# LionIRVT-PMP15043-2.net
KiCad netlist of a schematic drawn in Altium Designer
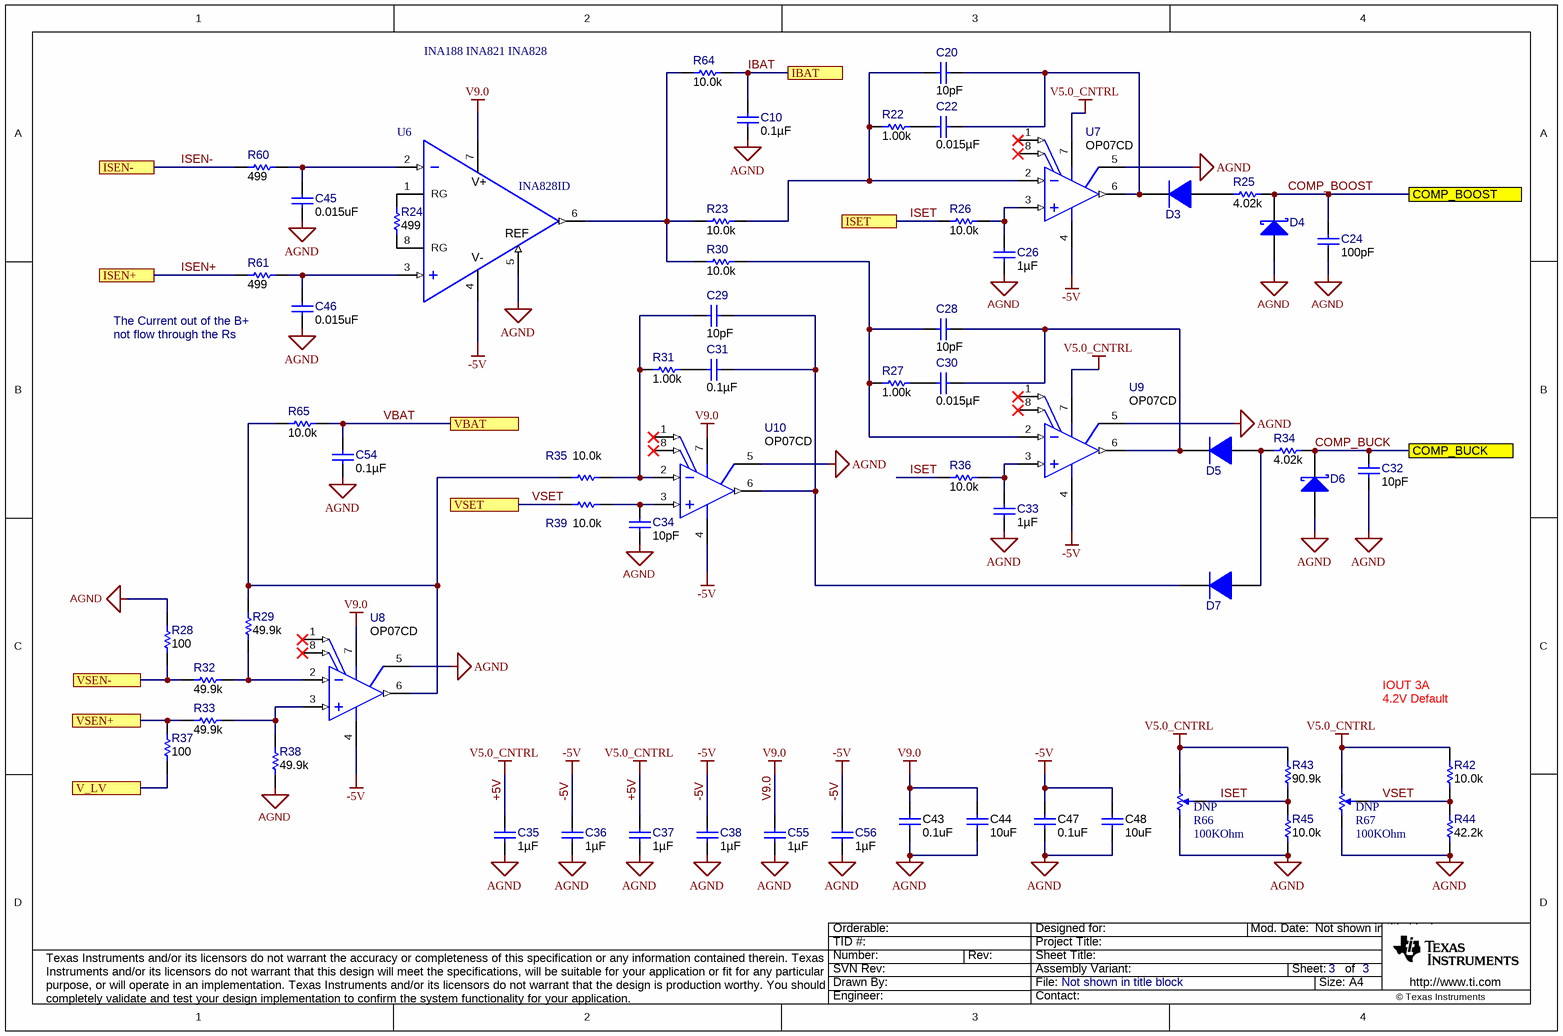
[diagram p0: LionIRVT-PMP15043-2.SchDoc]

(export (version "E")
  (design (tool "Eeschema 10.0.6"))
  (components
    (comp (ref "C10")
      (value "GRM155R61C104KA88D")
      (footprint "0402")
      (description "CAP, CERM, 0.1 µF, 16 V, +/- 10%, X5R, 0402")
      (fields
        (field (name "VALUEDISPLAYED") "0.1µF")
        (field (name "MANUFACTURER") "MuRata")
        (field (name "PUBLISHER") "Texas Instruments")
      )
      (libsource (lib "Capacitor_Ceramic") (part "GRM155R61C104KA88D"))
    )
    (comp (ref "C20")
      (value "GRM1555C1H100JA01D")
      (footprint "0402")
      (description "CAP, CERM, 10 pF, 50 V,+/- 5%, C0G/NP0, 0402")
      (fields
        (field (name "VALUEDISPLAYED") "10pF")
        (field (name "MANUFACTURER") "MuRata")
        (field (name "PUBLISHER") "Texas Instruments")
      )
      (libsource (lib "Capacitor_Ceramic") (part "GRM1555C1H100JA01D"))
    )
    (comp (ref "C22")
      (value "GRM155R71C153JA01D")
      (footprint "0402")
      (description "CAP, CERM, 0.015 µF, 16 V,+/- 5%, X7R, 0402")
      (fields
        (field (name "VALUEDISPLAYED") "0.015µF")
        (field (name "MANUFACTURER") "MuRata")
        (field (name "PUBLISHER") "Texas Instruments")
      )
      (libsource (lib "Capacitor_Ceramic") (part "GRM155R71C153JA01D"))
    )
    (comp (ref "C24")
      (value "GRM1555C1H101JA01D")
      (footprint "0402")
      (description "CAP, CERM, 100 pF, 50 V,+/- 5%, C0G/NP0, 0402")
      (fields
        (field (name "VALUEDISPLAYED") "100pF")
        (field (name "MANUFACTURER") "MuRata")
        (field (name "PUBLISHER") "Texas Instruments")
      )
      (libsource (lib "Capacitor_Ceramic") (part "GRM1555C1H101JA01D"))
    )
    (comp (ref "C26")
      (value "GRM155R70J105KA12D")
      (footprint "0402")
      (description "CAP, CERM, 1 µF, 6.3 V,+/- 10%, X7R, 0402")
      (fields
        (field (name "VALUEDISPLAYED") "1µF")
        (field (name "MANUFACTURER") "MuRata")
        (field (name "PUBLISHER") "Texas Instruments")
      )
      (libsource (lib "Capacitor_Ceramic") (part "GRM155R70J105KA12D"))
    )
    (comp (ref "C28")
      (value "GRM1555C1H100JA01D")
      (footprint "0402")
      (description "CAP, CERM, 10 pF, 50 V,+/- 5%, C0G/NP0, 0402")
      (fields
        (field (name "VALUEDISPLAYED") "10pF")
        (field (name "MANUFACTURER") "MuRata")
        (field (name "PUBLISHER") "Texas Instruments")
      )
      (libsource (lib "Capacitor_Ceramic") (part "GRM1555C1H100JA01D"))
    )
    (comp (ref "C29")
      (value "GRM1555C1H100JA01D")
      (footprint "0402")
      (description "CAP, CERM, 10 pF, 50 V,+/- 5%, C0G/NP0, 0402")
      (fields
        (field (name "VALUEDISPLAYED") "10pF")
        (field (name "MANUFACTURER") "MuRata")
        (field (name "PUBLISHER") "Texas Instruments")
      )
      (libsource (lib "Capacitor_Ceramic") (part "GRM1555C1H100JA01D"))
    )
    (comp (ref "C30")
      (value "GRM155R71C153JA01D")
      (footprint "0402")
      (description "CAP, CERM, 0.015 µF, 16 V,+/- 5%, X7R, 0402")
      (fields
        (field (name "VALUEDISPLAYED") "0.015µF")
        (field (name "MANUFACTURER") "MuRata")
        (field (name "PUBLISHER") "Texas Instruments")
      )
      (libsource (lib "Capacitor_Ceramic") (part "GRM155R71C153JA01D"))
    )
    (comp (ref "C31")
      (value "GRM155R61C104KA88D")
      (footprint "0402")
      (description "CAP, CERM, 0.1 µF, 16 V, +/- 10%, X5R, 0402")
      (fields
        (field (name "VALUEDISPLAYED") "0.1µF")
        (field (name "MANUFACTURER") "MuRata")
        (field (name "PUBLISHER") "Texas Instruments")
      )
      (libsource (lib "Capacitor_Ceramic") (part "GRM155R61C104KA88D"))
    )
    (comp (ref "C32")
      (value "GRM1555C1H100JA01D")
      (footprint "0402")
      (description "CAP, CERM, 10 pF, 50 V,+/- 5%, C0G/NP0, 0402")
      (fields
        (field (name "VALUEDISPLAYED") "10pF")
        (field (name "MANUFACTURER") "MuRata")
        (field (name "PUBLISHER") "Texas Instruments")
      )
      (libsource (lib "Capacitor_Ceramic") (part "GRM1555C1H100JA01D"))
    )
    (comp (ref "C33")
      (value "GRM155R70J105KA12D")
      (footprint "0402")
      (description "CAP, CERM, 1 µF, 6.3 V,+/- 10%, X7R, 0402")
      (fields
        (field (name "VALUEDISPLAYED") "1µF")
        (field (name "MANUFACTURER") "MuRata")
        (field (name "PUBLISHER") "Texas Instruments")
      )
      (libsource (lib "Capacitor_Ceramic") (part "GRM155R70J105KA12D"))
    )
    (comp (ref "C34")
      (value "GRM1555C1H100JA01D")
      (footprint "0402")
      (description "CAP, CERM, 10 pF, 50 V,+/- 5%, C0G/NP0, 0402")
      (fields
        (field (name "VALUEDISPLAYED") "10pF")
        (field (name "MANUFACTURER") "MuRata")
        (field (name "PUBLISHER") "Texas Instruments")
      )
      (libsource (lib "Capacitor_Ceramic") (part "GRM1555C1H100JA01D"))
    )
    (comp (ref "C35")
      (value "GRM155R61A105KE15D")
      (footprint "0402")
      (description "CAP, CERM, 1 µF, 10 V,+/- 10%, X5R, 0402")
      (fields
        (field (name "VALUEDISPLAYED") "1µF")
        (field (name "MANUFACTURER") "MuRata")
        (field (name "PUBLISHER") "Texas Instruments")
      )
      (libsource (lib "Capacitor_Ceramic") (part "GRM155R61A105KE15D"))
    )
    (comp (ref "C36")
      (value "GRM155R61A105KE15D")
      (footprint "0402")
      (description "CAP, CERM, 1 µF, 10 V,+/- 10%, X5R, 0402")
      (fields
        (field (name "VALUEDISPLAYED") "1µF")
        (field (name "MANUFACTURER") "MuRata")
        (field (name "PUBLISHER") "Texas Instruments")
      )
      (libsource (lib "Capacitor_Ceramic") (part "GRM155R61A105KE15D"))
    )
    (comp (ref "C37")
      (value "GRM155R61A105KE15D")
      (footprint "0402")
      (description "CAP, CERM, 1 µF, 10 V,+/- 10%, X5R, 0402")
      (fields
        (field (name "VALUEDISPLAYED") "1µF")
        (field (name "MANUFACTURER") "MuRata")
        (field (name "PUBLISHER") "Texas Instruments")
      )
      (libsource (lib "Capacitor_Ceramic") (part "GRM155R61A105KE15D"))
    )
    (comp (ref "C38")
      (value "GRM155R61A105KE15D")
      (footprint "0402")
      (description "CAP, CERM, 1 µF, 10 V,+/- 10%, X5R, 0402")
      (fields
        (field (name "VALUEDISPLAYED") "1µF")
        (field (name "MANUFACTURER") "MuRata")
        (field (name "PUBLISHER") "Texas Instruments")
      )
      (libsource (lib "Capacitor_Ceramic") (part "GRM155R61A105KE15D"))
    )
    (comp (ref "C43")
      (value "Capacitor")
      (footprint "0603")
      (description "CAP, CERM, 0.1 uF, 25 V, +/- 5%, X7R, 0603")
      (fields
        (field (name "PARTNUMBER") "06033C104JAT2A")
        (field (name "VALUEDISPLAYED") "0.1uF")
        (field (name "MANUFACTURER") "AVX")
        (field (name "PUBLISHER") "Texas Instruments")
      )
      (libsource (lib "Altium Vault - TI") (part "CMP-0006752-5"))
    )
    (comp (ref "C44")
      (value "Capacitor")
      (footprint "0805_HV")
      (description "CAP, CERM, 10 uF, 10 V, +/- 10%, X7R, 0805")
      (fields
        (field (name "PARTNUMBER") "GRM21BR71A106KE51L")
        (field (name "VALUEDISPLAYED") "10uF")
        (field (name "MANUFACTURER") "MuRata")
        (field (name "PUBLISHER") "Texas Instruments")
      )
      (libsource (lib "Altium Vault - TI") (part "CMP-0008315-2"))
    )
    (comp (ref "C45")
      (value "Capacitor")
      (footprint "0603")
      (description "CAP, CERM, 0.015 uF, 16 V, +/- 10%, X7R, 0603")
      (fields
        (field (name "PARTNUMBER") "GRM188R71C153KA01D")
        (field (name "VALUEDISPLAYED") "0.015uF")
        (field (name "MANUFACTURER") "MuRata")
        (field (name "PUBLISHER") "Texas Instruments")
      )
      (libsource (lib "Altium Vault - TI") (part "CMP-0007383-5"))
    )
    (comp (ref "C46")
      (value "Capacitor")
      (footprint "0603")
      (description "CAP, CERM, 0.015 uF, 16 V, +/- 10%, X7R, 0603")
      (fields
        (field (name "PARTNUMBER") "GRM188R71C153KA01D")
        (field (name "VALUEDISPLAYED") "0.015uF")
        (field (name "MANUFACTURER") "MuRata")
        (field (name "PUBLISHER") "Texas Instruments")
      )
      (libsource (lib "Altium Vault - TI") (part "CMP-0007383-5"))
    )
    (comp (ref "C47")
      (value "Capacitor")
      (footprint "0603")
      (description "CAP, CERM, 0.1 uF, 25 V, +/- 5%, X7R, 0603")
      (fields
        (field (name "PARTNUMBER") "06033C104JAT2A")
        (field (name "VALUEDISPLAYED") "0.1uF")
        (field (name "MANUFACTURER") "AVX")
        (field (name "PUBLISHER") "Texas Instruments")
      )
      (libsource (lib "Altium Vault - TI") (part "CMP-0006752-5"))
    )
    (comp (ref "C48")
      (value "Capacitor")
      (footprint "0805_HV")
      (description "CAP, CERM, 10 uF, 10 V, +/- 10%, X7R, 0805")
      (fields
        (field (name "PARTNUMBER") "GRM21BR71A106KE51L")
        (field (name "VALUEDISPLAYED") "10uF")
        (field (name "MANUFACTURER") "MuRata")
        (field (name "PUBLISHER") "Texas Instruments")
      )
      (libsource (lib "Altium Vault - TI") (part "CMP-0008315-2"))
    )
    (comp (ref "C54")
      (value "GRM155R61C104KA88D")
      (footprint "0402")
      (description "CAP, CERM, 0.1 µF, 16 V, +/- 10%, X5R, 0402")
      (fields
        (field (name "VALUEDISPLAYED") "0.1µF")
        (field (name "MANUFACTURER") "MuRata")
        (field (name "PUBLISHER") "Texas Instruments")
      )
      (libsource (lib "Capacitor_Ceramic") (part "GRM155R61C104KA88D"))
    )
    (comp (ref "C55")
      (value "GRM155R61A105KE15D")
      (footprint "0402")
      (description "CAP, CERM, 1 µF, 10 V,+/- 10%, X5R, 0402")
      (fields
        (field (name "VALUEDISPLAYED") "1µF")
        (field (name "MANUFACTURER") "MuRata")
        (field (name "PUBLISHER") "Texas Instruments")
      )
      (libsource (lib "Capacitor_Ceramic") (part "GRM155R61A105KE15D"))
    )
    (comp (ref "C56")
      (value "GRM155R61A105KE15D")
      (footprint "0402")
      (description "CAP, CERM, 1 µF, 10 V,+/- 10%, X5R, 0402")
      (fields
        (field (name "VALUEDISPLAYED") "1µF")
        (field (name "MANUFACTURER") "MuRata")
        (field (name "PUBLISHER") "Texas Instruments")
      )
      (libsource (lib "Capacitor_Ceramic") (part "GRM155R61A105KE15D"))
    )
    (comp (ref "D3")
      (value "1N4148X-TP")
      (footprint "SOD-523")
      (description "Diode, Switching, 75 V, 0.3 A, SOD-523")
      (fields
        (field (name "MANUFACTURER") "Micro Commercial Components")
        (field (name "PUBLISHER") "Texas Instruments")
      )
      (libsource (lib "Diode") (part "1N4148X-TP"))
    )
    (comp (ref "D4")
      (value "BAT54WS-7-F")
      (footprint "SOD-323")
      (description "Diode, Schottky, 30 V, 0.2 A, SOD-323")
      (fields (field (name "MANUFACTURER") "Diodes Inc.") (field (name "PUBLISHER") "Texas Instruments"))
      (libsource (lib "Diode") (part "BAT54WS-7-F"))
    )
    (comp (ref "D5")
      (value "1N4148X-TP")
      (footprint "SOD-523")
      (description "Diode, Switching, 75 V, 0.3 A, SOD-523")
      (fields
        (field (name "MANUFACTURER") "Micro Commercial Components")
        (field (name "PUBLISHER") "Texas Instruments")
      )
      (libsource (lib "Diode") (part "1N4148X-TP"))
    )
    (comp (ref "D6")
      (value "BAT54WS-7-F")
      (footprint "SOD-323")
      (description "Diode, Schottky, 30 V, 0.2 A, SOD-323")
      (fields (field (name "MANUFACTURER") "Diodes Inc.") (field (name "PUBLISHER") "Texas Instruments"))
      (libsource (lib "Diode") (part "BAT54WS-7-F"))
    )
    (comp (ref "D7")
      (value "1N4148X-TP")
      (footprint "SOD-523")
      (description "Diode, Switching, 75 V, 0.3 A, SOD-523")
      (fields
        (field (name "MANUFACTURER") "Micro Commercial Components")
        (field (name "PUBLISHER") "Texas Instruments")
      )
      (libsource (lib "Diode") (part "1N4148X-TP"))
    )
    (comp (ref "R22")
      (value "CRCW04021K00FKED")
      (footprint "0402")
      (description "RES, 1.00 k, 1%, 0.063 W, 0402")
      (fields
        (field (name "VALUEDISPLAYED") "1.00k")
        (field (name "MANUFACTURER") "Vishay-Dale")
        (field (name "PUBLISHER") "Texas Instruments")
      )
      (libsource (lib "Resistor_0402") (part "CRCW04021K00FKED"))
    )
    (comp (ref "R23")
      (value "CRCW040210K0FKED")
      (footprint "0402")
      (description "RES, 10.0 k, 1%, 0.063 W, 0402")
      (fields
        (field (name "VALUEDISPLAYED") "10.0k")
        (field (name "MANUFACTURER") "Vishay-Dale")
        (field (name "PUBLISHER") "Texas Instruments")
      )
      (libsource (lib "Resistor_0402") (part "CRCW040210K0FKED"))
    )
    (comp (ref "R24")
      (value "RC0603FR-07499RL")
      (footprint "0603")
      (description "RES, 499, 1%, 0.1 W, 0603")
      (fields
        (field (name "VALUEDISPLAYED") "499")
        (field (name "MANUFACTURER") "Yageo America")
        (field (name "PUBLISHER") "Texas Instruments")
      )
      (libsource (lib "Resistor_0603") (part "RC0603FR-07499RL"))
    )
    (comp (ref "R25")
      (value "CRCW04024K02FKED")
      (footprint "0402")
      (description "RES, 4.02 k, 1%, 0.063 W, 0402")
      (fields
        (field (name "VALUEDISPLAYED") "4.02k")
        (field (name "MANUFACTURER") "Vishay-Dale")
        (field (name "PUBLISHER") "Texas Instruments")
      )
      (libsource (lib "Resistor_0402") (part "CRCW04024K02FKED"))
    )
    (comp (ref "R26")
      (value "CRCW040210K0FKED")
      (footprint "0402")
      (description "RES, 10.0 k, 1%, 0.063 W, 0402")
      (fields
        (field (name "VALUEDISPLAYED") "10.0k")
        (field (name "MANUFACTURER") "Vishay-Dale")
        (field (name "PUBLISHER") "Texas Instruments")
      )
      (libsource (lib "Resistor_0402") (part "CRCW040210K0FKED"))
    )
    (comp (ref "R27")
      (value "CRCW04021K00FKED")
      (footprint "0402")
      (description "RES, 1.00 k, 1%, 0.063 W, 0402")
      (fields
        (field (name "VALUEDISPLAYED") "1.00k")
        (field (name "MANUFACTURER") "Vishay-Dale")
        (field (name "PUBLISHER") "Texas Instruments")
      )
      (libsource (lib "Resistor_0402") (part "CRCW04021K00FKED"))
    )
    (comp (ref "R28")
      (value "CRCW0402100RFKED")
      (footprint "0402")
      (description "RES, 100, 1%, 0.063 W, 0402")
      (fields
        (field (name "VALUEDISPLAYED") "100")
        (field (name "MANUFACTURER") "Vishay-Dale")
        (field (name "PUBLISHER") "Texas Instruments")
      )
      (libsource (lib "Resistor_0402") (part "CRCW0402100RFKED"))
    )
    (comp (ref "R29")
      (value "CRCW040251K1FKED")
      (footprint "0402")
      (description "RES, 51.1 k, 1%, 0.063 W, 0402")
      (fields
        (field (name "VALUEDISPLAYED") "49.9k")
        (field (name "MANUFACTURER") "Vishay-Dale")
        (field (name "PUBLISHER") "Texas Instruments")
      )
      (libsource (lib "Resistor_0402") (part "CRCW040251K1FKED"))
    )
    (comp (ref "R30")
      (value "CRCW040210K0FKED")
      (footprint "0402")
      (description "RES, 10.0 k, 1%, 0.063 W, 0402")
      (fields
        (field (name "VALUEDISPLAYED") "10.0k")
        (field (name "MANUFACTURER") "Vishay-Dale")
        (field (name "PUBLISHER") "Texas Instruments")
      )
      (libsource (lib "Resistor_0402") (part "CRCW040210K0FKED"))
    )
    (comp (ref "R31")
      (value "CRCW04021K00FKED")
      (footprint "0402")
      (description "RES, 1.00 k, 1%, 0.063 W, 0402")
      (fields
        (field (name "VALUEDISPLAYED") "1.00k")
        (field (name "MANUFACTURER") "Vishay-Dale")
        (field (name "PUBLISHER") "Texas Instruments")
      )
      (libsource (lib "Resistor_0402") (part "CRCW04021K00FKED"))
    )
    (comp (ref "R32")
      (value "CRCW040251K1FKED")
      (footprint "0402")
      (description "RES, 51.1 k, 1%, 0.063 W, 0402")
      (fields
        (field (name "VALUEDISPLAYED") "49.9k")
        (field (name "MANUFACTURER") "Vishay-Dale")
        (field (name "PUBLISHER") "Texas Instruments")
      )
      (libsource (lib "Resistor_0402") (part "CRCW040251K1FKED"))
    )
    (comp (ref "R33")
      (value "CRCW040251K1FKED")
      (footprint "0402")
      (description "RES, 51.1 k, 1%, 0.063 W, 0402")
      (fields
        (field (name "VALUEDISPLAYED") "49.9k")
        (field (name "MANUFACTURER") "Vishay-Dale")
        (field (name "PUBLISHER") "Texas Instruments")
      )
      (libsource (lib "Resistor_0402") (part "CRCW040251K1FKED"))
    )
    (comp (ref "R34")
      (value "CRCW04024K02FKED")
      (footprint "0402")
      (description "RES, 4.02 k, 1%, 0.063 W, 0402")
      (fields
        (field (name "VALUEDISPLAYED") "4.02k")
        (field (name "MANUFACTURER") "Vishay-Dale")
        (field (name "PUBLISHER") "Texas Instruments")
      )
      (libsource (lib "Resistor_0402") (part "CRCW04024K02FKED"))
    )
    (comp (ref "R35")
      (value "CRCW040210K0FKED")
      (footprint "0402")
      (description "RES, 10.0 k, 1%, 0.063 W, 0402")
      (fields
        (field (name "VALUEDISPLAYED") "10.0k")
        (field (name "MANUFACTURER") "Vishay-Dale")
        (field (name "PUBLISHER") "Texas Instruments")
      )
      (libsource (lib "Resistor_0402") (part "CRCW040210K0FKED"))
    )
    (comp (ref "R36")
      (value "CRCW040210K0FKED")
      (footprint "0402")
      (description "RES, 10.0 k, 1%, 0.063 W, 0402")
      (fields
        (field (name "VALUEDISPLAYED") "10.0k")
        (field (name "MANUFACTURER") "Vishay-Dale")
        (field (name "PUBLISHER") "Texas Instruments")
      )
      (libsource (lib "Resistor_0402") (part "CRCW040210K0FKED"))
    )
    (comp (ref "R37")
      (value "CRCW0402100RFKED")
      (footprint "0402")
      (description "RES, 100, 1%, 0.063 W, 0402")
      (fields
        (field (name "VALUEDISPLAYED") "100")
        (field (name "MANUFACTURER") "Vishay-Dale")
        (field (name "PUBLISHER") "Texas Instruments")
      )
      (libsource (lib "Resistor_0402") (part "CRCW0402100RFKED"))
    )
    (comp (ref "R38")
      (value "CRCW040251K1FKED")
      (footprint "0402")
      (description "RES, 51.1 k, 1%, 0.063 W, 0402")
      (fields
        (field (name "VALUEDISPLAYED") "49.9k")
        (field (name "MANUFACTURER") "Vishay-Dale")
        (field (name "PUBLISHER") "Texas Instruments")
      )
      (libsource (lib "Resistor_0402") (part "CRCW040251K1FKED"))
    )
    (comp (ref "R39")
      (value "CRCW040210K0FKED")
      (footprint "0402")
      (description "RES, 10.0 k, 1%, 0.063 W, 0402")
      (fields
        (field (name "VALUEDISPLAYED") "10.0k")
        (field (name "MANUFACTURER") "Vishay-Dale")
        (field (name "PUBLISHER") "Texas Instruments")
      )
      (libsource (lib "Resistor_0402") (part "CRCW040210K0FKED"))
    )
    (comp (ref "R42")
      (value "CRCW040210K0FKED")
      (footprint "0402")
      (description "RES, 10.0 k, 1%, 0.063 W, 0402")
      (fields
        (field (name "VALUEDISPLAYED") "10.0k")
        (field (name "MANUFACTURER") "Vishay-Dale")
        (field (name "PUBLISHER") "Texas Instruments")
      )
      (libsource (lib "Resistor_0402") (part "CRCW040210K0FKED"))
    )
    (comp (ref "R43")
      (value "CRCW040290K9FKED")
      (footprint "0402")
      (description "RES, 90.9 k, 1%, 0.063 W, 0402")
      (fields
        (field (name "VALUEDISPLAYED") "90.9k")
        (field (name "MANUFACTURER") "Vishay-Dale")
        (field (name "PUBLISHER") "Texas Instruments")
      )
      (libsource (lib "Resistor_0402") (part "CRCW040290K9FKED"))
    )
    (comp (ref "R44")
      (value "CRCW040242K2FKED")
      (footprint "0402")
      (description "RES, 42.2 k, 1%, 0.063 W, 0402")
      (fields
        (field (name "VALUEDISPLAYED") "42.2k")
        (field (name "MANUFACTURER") "Vishay-Dale")
        (field (name "PUBLISHER") "Texas Instruments")
      )
      (libsource (lib "Resistor_0402") (part "CRCW040242K2FKED"))
    )
    (comp (ref "R45")
      (value "CRCW040210K0FKED")
      (footprint "0402")
      (description "RES, 10.0 k, 1%, 0.063 W, 0402")
      (fields
        (field (name "VALUEDISPLAYED") "10.0k")
        (field (name "MANUFACTURER") "Vishay-Dale")
        (field (name "PUBLISHER") "Texas Instruments")
      )
      (libsource (lib "Resistor_0402") (part "CRCW040210K0FKED"))
    )
    (comp (ref "R60")
      (value "Resistor")
      (footprint "0603")
      (description "RES, 499, 1%, 0.1 W, AEC-Q200 Grade 0, 0603")
      (fields
        (field (name "PARTNUMBER") "CRCW0603499RFKEA")
        (field (name "VALUEDISPLAYED") "499")
        (field (name "MANUFACTURER") "Vishay-Dale")
      )
      (libsource (lib "Altium Vault - TI") (part "CMP-0022446-5"))
    )
    (comp (ref "R61")
      (value "Resistor")
      (footprint "0603")
      (description "RES, 499, 1%, 0.1 W, AEC-Q200 Grade 0, 0603")
      (fields
        (field (name "PARTNUMBER") "CRCW0603499RFKEA")
        (field (name "VALUEDISPLAYED") "499")
        (field (name "MANUFACTURER") "Vishay-Dale")
      )
      (libsource (lib "Altium Vault - TI") (part "CMP-0022446-5"))
    )
    (comp (ref "R64")
      (value "CRCW040210K0FKED")
      (footprint "0402")
      (description "RES, 10.0 k, 1%, 0.063 W, 0402")
      (fields
        (field (name "VALUEDISPLAYED") "10.0k")
        (field (name "MANUFACTURER") "Vishay-Dale")
        (field (name "PUBLISHER") "Texas Instruments")
      )
      (libsource (lib "Resistor_0402") (part "CRCW040210K0FKED"))
    )
    (comp (ref "R65")
      (value "CRCW040210K0FKED")
      (footprint "0402")
      (description "RES, 10.0 k, 1%, 0.063 W, 0402")
      (fields
        (field (name "VALUEDISPLAYED") "10.0k")
        (field (name "MANUFACTURER") "Vishay-Dale")
        (field (name "PUBLISHER") "Texas Instruments")
      )
      (libsource (lib "Resistor_0402") (part "CRCW040210K0FKED"))
    )
    (comp (ref "R66")
      (value "TC33X-2-104E")
      (footprint "BOUR-TC33X-2_V")
      (description "Trimming Potentiometer, 100000 Ohm, -40 to 100 degC, 3-Pin SMD, RoHS, Tape and Reel")
      (fields
        (field (name "TOLERANCE") "25%")
        (field (name "RESISTANCE") "100KOhm")
        (field (name "MANUFACTURER") "Bourns")
      )
      (libsource (lib "Altium Content Vault") (part "RES-ADJ-3_A"))
    )
    (comp (ref "R67")
      (value "TC33X-2-104E")
      (footprint "BOUR-TC33X-2_V")
      (description "Trimming Potentiometer, 100k Ohm, -40 to 100 degC, 3-Pin SMD, RoHS, Tape and Reel")
      (fields
        (field (name "TOLERANCE") "25%")
        (field (name "RESISTANCE") "100KOhm")
        (field (name "MANUFACTURER") "Bourns")
      )
      (libsource (lib "Altium Content Vault") (part "RES-ADJ-3_A"))
    )
    (comp (ref "U6")
      (value "INA828ID")
      (footprint "D0008A_N")
      (description "50-uV Offset, 7-nV/√Hz Noise, Low-Power, Precision Instrumentation Amplifier, D0008A (SOIC-8)")
      (fields
        (field (name "ALTERNATE PARTNUMBER") "INA828IDR")
        (field (name "MANUFACTURER") "Texas Instruments")
        (field (name "PARTNUMBER") "INA828ID")
      )
      (libsource (lib "Altium Vault - TI") (part "CMP-0079943-1"))
    )
    (comp (ref "U7")
      (value "OP07CD")
      (footprint "D0008A_N")
      (fields
        (field (name "ALTERNATE PARTNUMBER") "Equivalent")
        (field (name "MANUFACTURER") "Texas Instruments")
      )
      (libsource (lib "TI Amplifiers and Linear Operational Amplifier General Purpose") (part "OP07CD"))
    )
    (comp (ref "U8")
      (value "OP07CD")
      (footprint "D0008A_N")
      (fields
        (field (name "ALTERNATE PARTNUMBER") "Equivalent")
        (field (name "MANUFACTURER") "Texas Instruments")
      )
      (libsource (lib "TI Amplifiers and Linear Operational Amplifier General Purpose") (part "OP07CD"))
    )
    (comp (ref "U9")
      (value "OP07CD")
      (footprint "D0008A_N")
      (fields
        (field (name "ALTERNATE PARTNUMBER") "Equivalent")
        (field (name "MANUFACTURER") "Texas Instruments")
      )
      (libsource (lib "TI Amplifiers and Linear Operational Amplifier General Purpose") (part "OP07CD"))
    )
    (comp (ref "U10")
      (value "OP07CD")
      (footprint "D0008A_N")
      (fields
        (field (name "ALTERNATE PARTNUMBER") "Equivalent")
        (field (name "MANUFACTURER") "Texas Instruments")
      )
      (libsource (lib "TI Amplifiers and Linear Operational Amplifier General Purpose") (part "OP07CD"))
    )
  )
  (nets
    (net (code "1") (name "-5V") (class "Default")
      (node (ref "C36") (pin "1") (pinfunction "1_1") (pintype "passive"))
      (node (ref "C38") (pin "1") (pinfunction "1_1") (pintype "passive"))
      (node (ref "C47") (pin "1") (pinfunction "1_1") (pintype "passive"))
      (node (ref "C48") (pin "1") (pinfunction "1_1") (pintype "passive"))
      (node (ref "C56") (pin "1") (pinfunction "1_1") (pintype "passive"))
      (node (ref "U10") (pin "4") (pinfunction "VCC-_4") (pintype "power_in"))
      (node (ref "U6") (pin "4") (pinfunction "V-_4") (pintype "power_in"))
      (node (ref "U7") (pin "4") (pinfunction "VCC-_4") (pintype "power_in"))
      (node (ref "U8") (pin "4") (pinfunction "VCC-_4") (pintype "power_in"))
      (node (ref "U9") (pin "4") (pinfunction "VCC-_4") (pintype "power_in"))
    )
    (net (code "2") (name "/COMP_BOOST") (class "Default")
      (node (ref "C24") (pin "1") (pinfunction "1_1") (pintype "passive"))
      (node (ref "D4") (pin "1") (pinfunction "K_1") (pintype "passive"))
      (node (ref "R25") (pin "1") (pinfunction "1_1") (pintype "passive"))
    )
    (net (code "3") (name "/COMP_BUCK") (class "Default")
      (node (ref "C32") (pin "1") (pinfunction "1_1") (pintype "passive"))
      (node (ref "D6") (pin "1") (pinfunction "K_1") (pintype "passive"))
      (node (ref "R34") (pin "1") (pinfunction "1_1") (pintype "passive"))
    )
    (net (code "4") (name "/IBAT") (class "Default")
      (node (ref "C10") (pin "1") (pinfunction "1_1") (pintype "passive"))
      (node (ref "R64") (pin "2") (pinfunction "2_2") (pintype "passive"))
    )
    (net (code "5") (name "/ISEN+") (class "Default")
      (node (ref "R61") (pin "2") (pinfunction "2_2") (pintype "passive"))
    )
    (net (code "6") (name "/ISEN-") (class "Default")
      (node (ref "R60") (pin "2") (pinfunction "2_2") (pintype "passive"))
    )
    (net (code "7") (name "/ISET") (class "Default")
      (node (ref "R26") (pin "2") (pinfunction "2_2") (pintype "passive"))
      (node (ref "R36") (pin "2") (pinfunction "2_2") (pintype "passive"))
      (node (ref "R43") (pin "1") (pinfunction "1_1") (pintype "passive"))
      (node (ref "R45") (pin "2") (pinfunction "2_2") (pintype "passive"))
      (node (ref "R66") (pin "2") (pinfunction "2_2") (pintype "passive"))
    )
    (net (code "8") (name "/VBAT") (class "Default")
      (node (ref "C54") (pin "1") (pinfunction "1_1") (pintype "passive"))
      (node (ref "R65") (pin "2") (pinfunction "2_2") (pintype "passive"))
    )
    (net (code "9") (name "/VSEN+") (class "Default")
      (node (ref "R33") (pin "1") (pinfunction "1_1") (pintype "passive"))
      (node (ref "R37") (pin "2") (pinfunction "2_2") (pintype "passive"))
    )
    (net (code "10") (name "/VSEN-") (class "Default")
      (node (ref "R28") (pin "1") (pinfunction "1_1") (pintype "passive"))
      (node (ref "R32") (pin "1") (pinfunction "1_1") (pintype "passive"))
    )
    (net (code "11") (name "/VSET") (class "Default")
      (node (ref "R39") (pin "2") (pinfunction "2_2") (pintype "passive"))
      (node (ref "R42") (pin "1") (pinfunction "1_1") (pintype "passive"))
      (node (ref "R44") (pin "2") (pinfunction "2_2") (pintype "passive"))
      (node (ref "R67") (pin "2") (pinfunction "2_2") (pintype "passive"))
    )
    (net (code "12") (name "/V_LV") (class "Default")
      (node (ref "R37") (pin "1") (pinfunction "1_1") (pintype "passive"))
    )
    (net (code "13") (name "AGND") (class "Default")
      (node (ref "C10") (pin "2") (pinfunction "2_2") (pintype "passive"))
      (node (ref "C24") (pin "2") (pinfunction "2_2") (pintype "passive"))
      (node (ref "C26") (pin "2") (pinfunction "2_2") (pintype "passive"))
      (node (ref "C32") (pin "2") (pinfunction "2_2") (pintype "passive"))
      (node (ref "C33") (pin "2") (pinfunction "2_2") (pintype "passive"))
      (node (ref "C34") (pin "2") (pinfunction "2_2") (pintype "passive"))
      (node (ref "C35") (pin "2") (pinfunction "2_2") (pintype "passive"))
      (node (ref "C36") (pin "2") (pinfunction "2_2") (pintype "passive"))
      (node (ref "C37") (pin "2") (pinfunction "2_2") (pintype "passive"))
      (node (ref "C38") (pin "2") (pinfunction "2_2") (pintype "passive"))
      (node (ref "C43") (pin "2") (pinfunction "2_2") (pintype "passive"))
      (node (ref "C44") (pin "2") (pinfunction "2_2") (pintype "passive"))
      (node (ref "C45") (pin "2") (pinfunction "2_2") (pintype "passive"))
      (node (ref "C46") (pin "2") (pinfunction "2_2") (pintype "passive"))
      (node (ref "C47") (pin "2") (pinfunction "2_2") (pintype "passive"))
      (node (ref "C48") (pin "2") (pinfunction "2_2") (pintype "passive"))
      (node (ref "C54") (pin "2") (pinfunction "2_2") (pintype "passive"))
      (node (ref "C55") (pin "2") (pinfunction "2_2") (pintype "passive"))
      (node (ref "C56") (pin "2") (pinfunction "2_2") (pintype "passive"))
      (node (ref "D4") (pin "2") (pinfunction "A_2") (pintype "passive"))
      (node (ref "D6") (pin "2") (pinfunction "A_2") (pintype "passive"))
      (node (ref "R28") (pin "2") (pinfunction "2_2") (pintype "passive"))
      (node (ref "R38") (pin "1") (pinfunction "1_1") (pintype "passive"))
      (node (ref "R44") (pin "1") (pinfunction "1_1") (pintype "passive"))
      (node (ref "R45") (pin "1") (pinfunction "1_1") (pintype "passive"))
      (node (ref "R66") (pin "1") (pinfunction "1_1") (pintype "passive"))
      (node (ref "R67") (pin "1") (pinfunction "1_1") (pintype "passive"))
      (node (ref "U10") (pin "5") (pinfunction "NC_5") (pintype "passive"))
      (node (ref "U6") (pin "5") (pinfunction "REF_5") (pintype "input"))
      (node (ref "U7") (pin "5") (pinfunction "NC_5") (pintype "passive"))
      (node (ref "U8") (pin "5") (pinfunction "NC_5") (pintype "passive"))
      (node (ref "U9") (pin "5") (pinfunction "NC_5") (pintype "passive"))
    )
    (net (code "14") (name "Net-(C22-Pad2)") (class "Default")
      (node (ref "C22") (pin "2") (pinfunction "2_2") (pintype "passive"))
      (node (ref "R22") (pin "2") (pinfunction "2_2") (pintype "passive"))
    )
    (net (code "15") (name "Net-(C30-Pad2)") (class "Default")
      (node (ref "C30") (pin "2") (pinfunction "2_2") (pintype "passive"))
      (node (ref "R27") (pin "2") (pinfunction "2_2") (pintype "passive"))
    )
    (net (code "16") (name "Net-(C31-Pad2)") (class "Default")
      (node (ref "C31") (pin "2") (pinfunction "2_2") (pintype "passive"))
      (node (ref "R31") (pin "2") (pinfunction "2_2") (pintype "passive"))
    )
    (net (code "17") (name "Net-(D3-A)") (class "Default")
      (node (ref "D3") (pin "2") (pinfunction "A_2") (pintype "passive"))
      (node (ref "R25") (pin "2") (pinfunction "2_2") (pintype "passive"))
    )
    (net (code "18") (name "Net-(D3-K)") (class "Default")
      (node (ref "C20") (pin "1") (pinfunction "1_1") (pintype "passive"))
      (node (ref "C22") (pin "1") (pinfunction "1_1") (pintype "passive"))
      (node (ref "D3") (pin "1") (pinfunction "K_1") (pintype "passive"))
      (node (ref "U7") (pin "6") (pinfunction "OUT_6") (pintype "output"))
    )
    (net (code "19") (name "Net-(D5-A)") (class "Default")
      (node (ref "D5") (pin "2") (pinfunction "A_2") (pintype "passive"))
      (node (ref "D7") (pin "2") (pinfunction "A_2") (pintype "passive"))
      (node (ref "R34") (pin "2") (pinfunction "2_2") (pintype "passive"))
    )
    (net (code "20") (name "Net-(D5-K)") (class "Default")
      (node (ref "C28") (pin "1") (pinfunction "1_1") (pintype "passive"))
      (node (ref "C30") (pin "1") (pinfunction "1_1") (pintype "passive"))
      (node (ref "D5") (pin "1") (pinfunction "K_1") (pintype "passive"))
      (node (ref "U9") (pin "6") (pinfunction "OUT_6") (pintype "output"))
    )
    (net (code "21") (name "Net-(D7-K)") (class "Default")
      (node (ref "C29") (pin "1") (pinfunction "1_1") (pintype "passive"))
      (node (ref "C31") (pin "1") (pinfunction "1_1") (pintype "passive"))
      (node (ref "D7") (pin "1") (pinfunction "K_1") (pintype "passive"))
      (node (ref "U10") (pin "6") (pinfunction "OUT_6") (pintype "output"))
    )
    (net (code "22") (name "Net-(R24-Pad1)") (class "Default")
      (node (ref "R24") (pin "1") (pinfunction "1_1") (pintype "passive"))
      (node (ref "U6") (pin "8") (pinfunction "RG_8") (pintype "passive"))
    )
    (net (code "23") (name "Net-(R24-Pad2)") (class "Default")
      (node (ref "R24") (pin "2") (pinfunction "2_2") (pintype "passive"))
      (node (ref "U6") (pin "1") (pinfunction "RG_1") (pintype "passive"))
    )
    (net (code "24") (name "Net-(U6-IN+)") (class "Default")
      (node (ref "C46") (pin "1") (pinfunction "1_1") (pintype "passive"))
      (node (ref "R61") (pin "1") (pinfunction "1_1") (pintype "passive"))
      (node (ref "U6") (pin "3") (pinfunction "IN+_3") (pintype "input"))
    )
    (net (code "25") (name "Net-(U6-IN-)") (class "Default")
      (node (ref "C45") (pin "1") (pinfunction "1_1") (pintype "passive"))
      (node (ref "R60") (pin "1") (pinfunction "1_1") (pintype "passive"))
      (node (ref "U6") (pin "2") (pinfunction "IN-_2") (pintype "input"))
    )
    (net (code "26") (name "Net-(U6-OUT)") (class "Default")
      (node (ref "R23") (pin "2") (pinfunction "2_2") (pintype "passive"))
      (node (ref "R30") (pin "1") (pinfunction "1_1") (pintype "passive"))
      (node (ref "R64") (pin "1") (pinfunction "1_1") (pintype "passive"))
      (node (ref "U6") (pin "6") (pinfunction "OUT_6") (pintype "output"))
    )
    (net (code "27") (name "Net-(U7-IN+)") (class "Default")
      (node (ref "C26") (pin "1") (pinfunction "1_1") (pintype "passive"))
      (node (ref "R26") (pin "1") (pinfunction "1_1") (pintype "passive"))
      (node (ref "U7") (pin "3") (pinfunction "IN+_3") (pintype "input"))
    )
    (net (code "28") (name "Net-(U7-IN-)") (class "Default")
      (node (ref "C20") (pin "2") (pinfunction "2_2") (pintype "passive"))
      (node (ref "R22") (pin "1") (pinfunction "1_1") (pintype "passive"))
      (node (ref "R23") (pin "1") (pinfunction "1_1") (pintype "passive"))
      (node (ref "U7") (pin "2") (pinfunction "IN-_2") (pintype "input"))
    )
    (net (code "29") (name "Net-(U8-IN+)") (class "Default")
      (node (ref "R33") (pin "2") (pinfunction "2_2") (pintype "passive"))
      (node (ref "R38") (pin "2") (pinfunction "2_2") (pintype "passive"))
      (node (ref "U8") (pin "3") (pinfunction "IN+_3") (pintype "input"))
    )
    (net (code "30") (name "Net-(U8-IN-)") (class "Default")
      (node (ref "R29") (pin "1") (pinfunction "1_1") (pintype "passive"))
      (node (ref "R32") (pin "2") (pinfunction "2_2") (pintype "passive"))
      (node (ref "U8") (pin "2") (pinfunction "IN-_2") (pintype "input"))
    )
    (net (code "31") (name "Net-(U8-OUT)") (class "Default")
      (node (ref "R29") (pin "2") (pinfunction "2_2") (pintype "passive"))
      (node (ref "R35") (pin "1") (pinfunction "1_1") (pintype "passive"))
      (node (ref "R65") (pin "1") (pinfunction "1_1") (pintype "passive"))
      (node (ref "U8") (pin "6") (pinfunction "OUT_6") (pintype "output"))
    )
    (net (code "32") (name "Net-(U9-IN+)") (class "Default")
      (node (ref "C33") (pin "1") (pinfunction "1_1") (pintype "passive"))
      (node (ref "R36") (pin "1") (pinfunction "1_1") (pintype "passive"))
      (node (ref "U9") (pin "3") (pinfunction "IN+_3") (pintype "input"))
    )
    (net (code "33") (name "Net-(U9-IN-)") (class "Default")
      (node (ref "C28") (pin "2") (pinfunction "2_2") (pintype "passive"))
      (node (ref "R27") (pin "1") (pinfunction "1_1") (pintype "passive"))
      (node (ref "R30") (pin "2") (pinfunction "2_2") (pintype "passive"))
      (node (ref "U9") (pin "2") (pinfunction "IN-_2") (pintype "input"))
    )
    (net (code "34") (name "Net-(U10-IN+)") (class "Default")
      (node (ref "C34") (pin "1") (pinfunction "1_1") (pintype "passive"))
      (node (ref "R39") (pin "1") (pinfunction "1_1") (pintype "passive"))
      (node (ref "U10") (pin "3") (pinfunction "IN+_3") (pintype "input"))
    )
    (net (code "35") (name "Net-(U10-IN-)") (class "Default")
      (node (ref "C29") (pin "2") (pinfunction "2_2") (pintype "passive"))
      (node (ref "R31") (pin "1") (pinfunction "1_1") (pintype "passive"))
      (node (ref "R35") (pin "2") (pinfunction "2_2") (pintype "passive"))
      (node (ref "U10") (pin "2") (pinfunction "IN-_2") (pintype "input"))
    )
    (net (code "36") (name "V5.0_CNTRL") (class "Default")
      (node (ref "C35") (pin "1") (pinfunction "1_1") (pintype "passive"))
      (node (ref "C37") (pin "1") (pinfunction "1_1") (pintype "passive"))
      (node (ref "R42") (pin "2") (pinfunction "2_2") (pintype "passive"))
      (node (ref "R43") (pin "2") (pinfunction "2_2") (pintype "passive"))
      (node (ref "R66") (pin "3") (pinfunction "3_3") (pintype "passive"))
      (node (ref "R67") (pin "3") (pinfunction "3_3") (pintype "passive"))
      (node (ref "U7") (pin "7") (pinfunction "VCC+_7") (pintype "power_in"))
      (node (ref "U9") (pin "7") (pinfunction "VCC+_7") (pintype "power_in"))
    )
    (net (code "37") (name "V9.0") (class "Default")
      (node (ref "C43") (pin "1") (pinfunction "1_1") (pintype "passive"))
      (node (ref "C44") (pin "1") (pinfunction "1_1") (pintype "passive"))
      (node (ref "C55") (pin "1") (pinfunction "1_1") (pintype "passive"))
      (node (ref "U10") (pin "7") (pinfunction "VCC+_7") (pintype "power_in"))
      (node (ref "U6") (pin "7") (pinfunction "V+_7") (pintype "power_in"))
      (node (ref "U8") (pin "7") (pinfunction "VCC+_7") (pintype "power_in"))
    )
    (net (code "38") (name "unconnected-(U7-OFFSET_N1-Pad1)") (class "Default")
      (node (ref "U7") (pin "1") (pinfunction "OFFSET_N1_1") (pintype "input+no_connect"))
    )
    (net (code "39") (name "unconnected-(U7-OFFSET_N2-Pad8)") (class "Default")
      (node (ref "U7") (pin "8") (pinfunction "OFFSET_N2_8") (pintype "input+no_connect"))
    )
    (net (code "40") (name "unconnected-(U8-OFFSET_N1-Pad1)") (class "Default")
      (node (ref "U8") (pin "1") (pinfunction "OFFSET_N1_1") (pintype "input+no_connect"))
    )
    (net (code "41") (name "unconnected-(U8-OFFSET_N2-Pad8)") (class "Default")
      (node (ref "U8") (pin "8") (pinfunction "OFFSET_N2_8") (pintype "input+no_connect"))
    )
    (net (code "42") (name "unconnected-(U9-OFFSET_N1-Pad1)") (class "Default")
      (node (ref "U9") (pin "1") (pinfunction "OFFSET_N1_1") (pintype "input+no_connect"))
    )
    (net (code "43") (name "unconnected-(U9-OFFSET_N2-Pad8)") (class "Default")
      (node (ref "U9") (pin "8") (pinfunction "OFFSET_N2_8") (pintype "input+no_connect"))
    )
    (net (code "44") (name "unconnected-(U10-OFFSET_N1-Pad1)") (class "Default")
      (node (ref "U10") (pin "1") (pinfunction "OFFSET_N1_1") (pintype "input+no_connect"))
    )
    (net (code "45") (name "unconnected-(U10-OFFSET_N2-Pad8)") (class "Default")
      (node (ref "U10") (pin "8") (pinfunction "OFFSET_N2_8") (pintype "input+no_connect"))
    )
  )
)
